# senderNode_tiny84.net
KiCad netlist of a schematic drawn in EAGLE
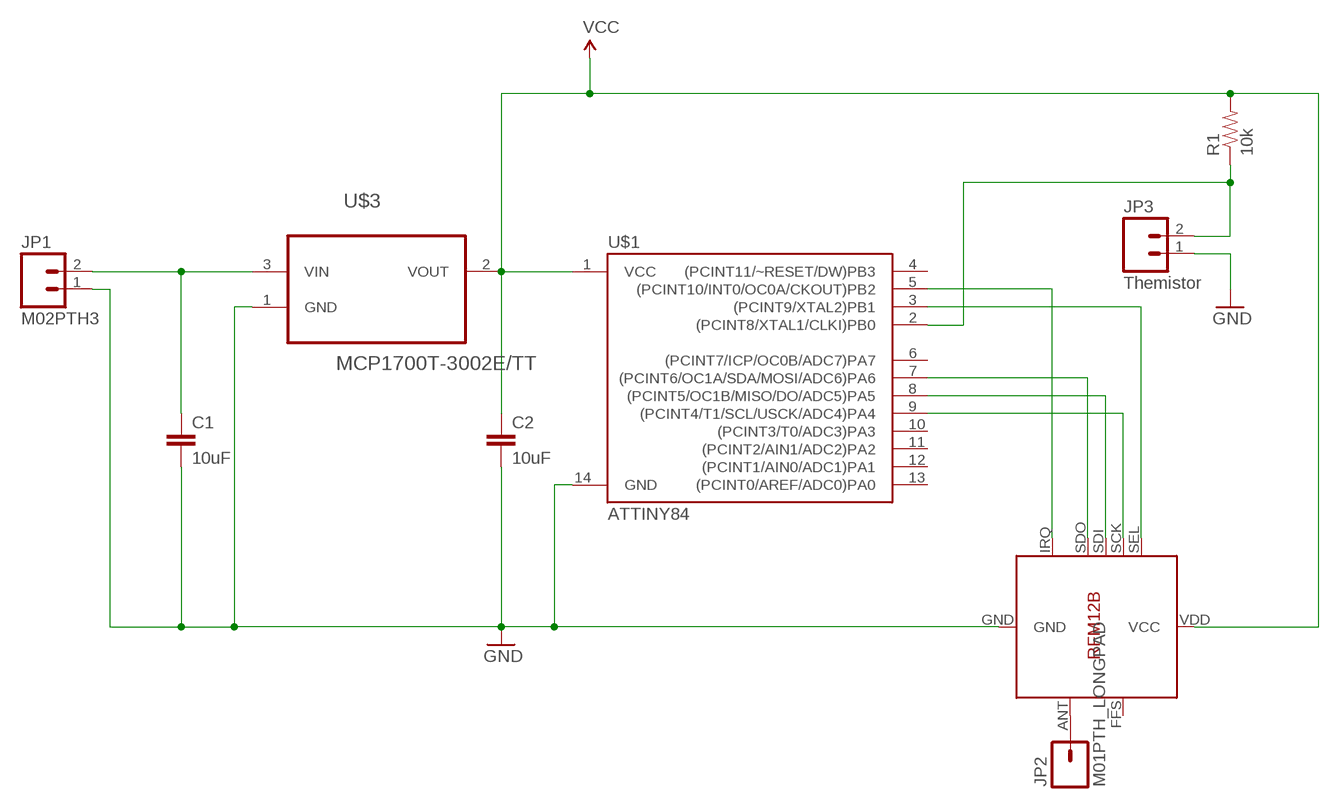
[diagram p0: schematic, sheet 1]

(export (version "E")
  (design (tool "Eeschema 10.0.6"))
  (components
    (comp (ref "C1")
      (value "10uF")
      (footprint "eagle-import:0603-CAP")
      (libsource (lib "eagle-import") (part "10UF-6.3V-20%(0603)"))
    )
    (comp (ref "C2")
      (value "10uF")
      (footprint "eagle-import:0603-CAP")
      (libsource (lib "eagle-import") (part "10UF-6.3V-20%(0603)"))
    )
    (comp (ref "JP1")
      (value "M02PTH3")
      (footprint "eagle-import:1X02_LONGPADS")
      (libsource (lib "eagle-import") (part "M02PTH3"))
    )
    (comp (ref "JP2")
      (value "M01PTH_LONGPAD")
      (footprint "eagle-import:1X01_LONGPAD")
      (libsource (lib "eagle-import") (part "M01PTH_LONGPAD"))
    )
    (comp (ref "JP3")
      (value "Themistor")
      (footprint "eagle-import:1X02_LONGPADS")
      (libsource (lib "eagle-import") (part "M02PTH3"))
    )
    (comp (ref "R1")
      (value "10k")
      (footprint "eagle-import:0805")
      (libsource (lib "eagle-import") (part "RESISTOR0805-RES"))
    )
    (comp (ref "U$1")
      (value "ATTINY84")
      (footprint "eagle-import:SO14")
      (libsource (lib "eagle-import") (part "ATTINY84"))
    )
    (comp (ref "U$2")
      (value "RFM12B")
      (footprint "eagle-import:RFM12B")
      (libsource (lib "eagle-import") (part "RFM12B"))
    )
    (comp (ref "U$3")
      (value "MCP1700T-3002E/TT")
      (footprint "eagle-import:SOT95P237X112-3N")
      (libsource (lib "eagle-import") (part "MCP1700T-3002E/TT"))
    )
  )
  (nets
    (net (code "1") (name "GND") (class "Default")
      (node (ref "C1") (pin "2") (pinfunction "2_2") (pintype "passive"))
      (node (ref "C2") (pin "2") (pinfunction "2_2") (pintype "passive"))
      (node (ref "JP1") (pin "1") (pinfunction "1_1") (pintype "passive"))
      (node (ref "JP3") (pin "1") (pinfunction "1_1") (pintype "passive"))
      (node (ref "U$1") (pin "14") (pinfunction "GND_14") (pintype "bidirectional"))
      (node (ref "U$2") (pin "GND") (pinfunction "GND_GND") (pintype "power_in"))
      (node (ref "U$3") (pin "1") (pinfunction "GND_1") (pintype "passive"))
    )
    (net (code "2") (name "Net-(JP2-Pad1)") (class "Default")
      (node (ref "JP2") (pin "1") (pinfunction "1_1") (pintype "passive"))
      (node (ref "U$2") (pin "ANT") (pinfunction "ANT_ANT") (pintype "passive"))
    )
    (net (code "3") (name "Net-(U$1-(PCINT4{slash}T1{slash}SCL{slash}USCK{slash}ADC4)PA4)") (class "Default")
      (node (ref "U$1") (pin "9") (pinfunction "(PCINT4/T1/SCL/USCK/ADC4)PA4_9") (pintype "bidirectional"))
      (node (ref "U$2") (pin "SCK") (pinfunction "SCK_SCK") (pintype "input"))
    )
    (net (code "4") (name "Net-(U$1-(PCINT5{slash}OC1B{slash}MISO{slash}DO{slash}ADC5)PA5)") (class "Default")
      (node (ref "U$1") (pin "8") (pinfunction "(PCINT5/OC1B/MISO/DO/ADC5)PA5_8") (pintype "bidirectional"))
      (node (ref "U$2") (pin "SDI") (pinfunction "SDI_SDI") (pintype "input"))
    )
    (net (code "5") (name "Net-(U$1-(PCINT6{slash}OC1A{slash}SDA{slash}MOSI{slash}ADC6)PA6)") (class "Default")
      (node (ref "U$1") (pin "7") (pinfunction "(PCINT6/OC1A/SDA/MOSI/ADC6)PA6_7") (pintype "bidirectional"))
      (node (ref "U$2") (pin "SDO") (pinfunction "SDO_SDO") (pintype "output"))
    )
    (net (code "6") (name "Net-(U$1-(PCINT8{slash}XTAL1{slash}CLKI)PB0)") (class "Default")
      (node (ref "JP3") (pin "2") (pinfunction "2_2") (pintype "passive"))
      (node (ref "R1") (pin "1") (pinfunction "1_1") (pintype "passive"))
      (node (ref "U$1") (pin "2") (pinfunction "(PCINT8/XTAL1/CLKI)PB0_2") (pintype "bidirectional"))
    )
    (net (code "7") (name "Net-(U$1-(PCINT9{slash}XTAL2)PB1)") (class "Default")
      (node (ref "U$1") (pin "3") (pinfunction "(PCINT9/XTAL2)PB1_3") (pintype "bidirectional"))
      (node (ref "U$2") (pin "SEL") (pinfunction "SEL_SEL") (pintype "input"))
    )
    (net (code "8") (name "Net-(U$1-(PCINT10{slash}INT0{slash}OC0A{slash}CKOUT)PB2)") (class "Default")
      (node (ref "U$1") (pin "5") (pinfunction "(PCINT10/INT0/OC0A/CKOUT)PB2_5") (pintype "bidirectional"))
      (node (ref "U$2") (pin "IRQ") (pinfunction "IRQ_IRQ") (pintype "open_collector"))
    )
    (net (code "9") (name "Net-(U$3-VIN)") (class "Default")
      (node (ref "C1") (pin "1") (pinfunction "1_1") (pintype "passive"))
      (node (ref "JP1") (pin "2") (pinfunction "2_2") (pintype "passive"))
      (node (ref "U$3") (pin "3") (pinfunction "VIN_3") (pintype "input"))
    )
    (net (code "10") (name "VCC") (class "Default")
      (node (ref "C2") (pin "1") (pinfunction "1_1") (pintype "passive"))
      (node (ref "R1") (pin "2") (pinfunction "2_2") (pintype "passive"))
      (node (ref "U$1") (pin "1") (pinfunction "VCC_1") (pintype "bidirectional"))
      (node (ref "U$2") (pin "VDD") (pinfunction "VCC_VDD") (pintype "power_in"))
      (node (ref "U$3") (pin "2") (pinfunction "VOUT_2") (pintype "output"))
    )
    (net (code "11") (name "unconnected-(U$1-(PCINT0{slash}AREF{slash}ADC0)PA0-Pad13)") (class "Default")
      (node (ref "U$1") (pin "13") (pinfunction "(PCINT0/AREF/ADC0)PA0_13") (pintype "bidirectional"))
    )
    (net (code "12") (name "unconnected-(U$1-(PCINT1{slash}AIN0{slash}ADC1)PA1-Pad12)") (class "Default")
      (node (ref "U$1") (pin "12") (pinfunction "(PCINT1/AIN0/ADC1)PA1_12") (pintype "bidirectional"))
    )
    (net (code "13") (name "unconnected-(U$1-(PCINT2{slash}AIN1{slash}ADC2)PA2-Pad11)") (class "Default")
      (node (ref "U$1") (pin "11") (pinfunction "(PCINT2/AIN1/ADC2)PA2_11") (pintype "bidirectional"))
    )
    (net (code "14") (name "unconnected-(U$1-(PCINT3{slash}T0{slash}ADC3)PA3-Pad10)") (class "Default")
      (node (ref "U$1") (pin "10") (pinfunction "(PCINT3/T0/ADC3)PA3_10") (pintype "bidirectional"))
    )
    (net (code "15") (name "unconnected-(U$1-(PCINT7{slash}ICP{slash}OC0B{slash}ADC7)PA7-Pad6)") (class "Default")
      (node (ref "U$1") (pin "6") (pinfunction "(PCINT7/ICP/OC0B/ADC7)PA7_6") (pintype "bidirectional"))
    )
    (net (code "16") (name "unconnected-(U$1-(PCINT11{slash}~{RESET{slash}DW})PB3-Pad4)") (class "Default")
      (node (ref "U$1") (pin "4") (pinfunction "(PCINT11/~{RESET/DW})PB3_4") (pintype "bidirectional"))
    )
    (net (code "17") (name "unconnected-(U$2-PadFFS)") (class "Default")
      (node (ref "U$2") (pin "FFS") (pinfunction "FFS_FFS") (pintype "bidirectional"))
    )
  )
)
